# open-race-scale-pi-zero-board-v_02.net
KiCad netlist of a schematic drawn in EAGLE
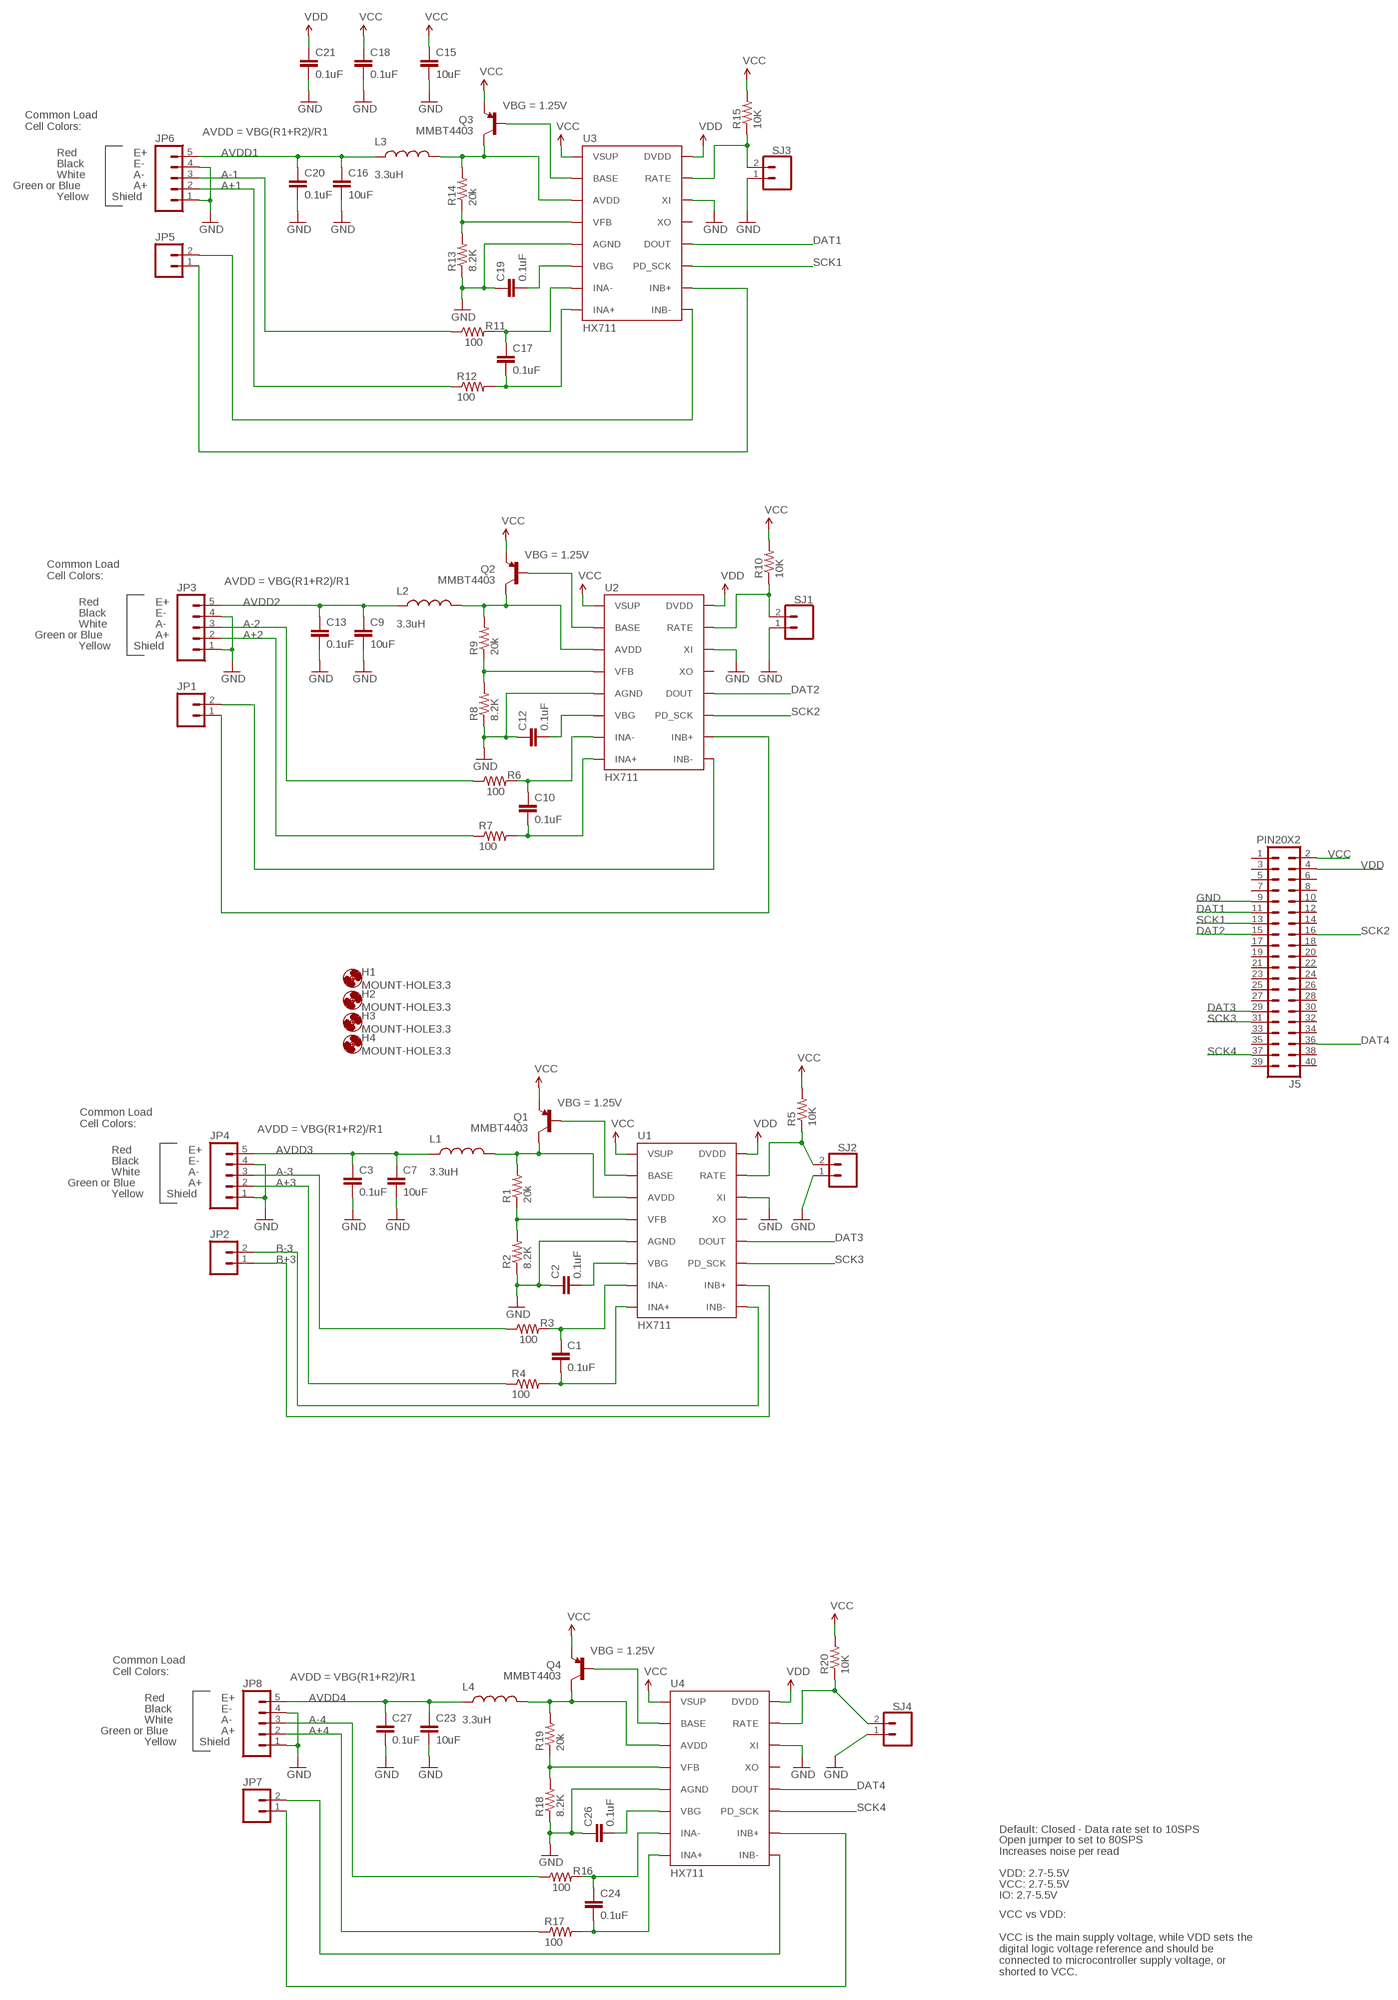
[diagram p0: schematic, sheet 1]

(export (version "E")
  (design (tool "Eeschema 10.0.6"))
  (components
    (comp (ref "C1")
      (value "0.1uF")
      (footprint "eagle-import:0603-CAP")
      (libsource (lib "eagle-import") (part "0.1UF-25V-5%(0603)"))
    )
    (comp (ref "C2")
      (value "0.1uF")
      (footprint "eagle-import:0603-CAP")
      (libsource (lib "eagle-import") (part "0.1UF-25V-5%(0603)"))
    )
    (comp (ref "C3")
      (value "0.1uF")
      (footprint "eagle-import:0603-CAP")
      (libsource (lib "eagle-import") (part "0.1UF-25V-5%(0603)"))
    )
    (comp (ref "C7")
      (value "10uF")
      (footprint "eagle-import:1210")
      (libsource (lib "eagle-import") (part "10UF50V20%(1210)"))
    )
    (comp (ref "C9")
      (value "10uF")
      (footprint "eagle-import:1210")
      (libsource (lib "eagle-import") (part "10UF50V20%(1210)"))
    )
    (comp (ref "C10")
      (value "0.1uF")
      (footprint "eagle-import:0603-CAP")
      (libsource (lib "eagle-import") (part "0.1UF-25V-5%(0603)"))
    )
    (comp (ref "C12")
      (value "0.1uF")
      (footprint "eagle-import:0603-CAP")
      (libsource (lib "eagle-import") (part "0.1UF-25V-5%(0603)"))
    )
    (comp (ref "C13")
      (value "0.1uF")
      (footprint "eagle-import:0603-CAP")
      (libsource (lib "eagle-import") (part "0.1UF-25V-5%(0603)"))
    )
    (comp (ref "C15")
      (value "10uF")
      (footprint "eagle-import:1210")
      (libsource (lib "eagle-import") (part "10UF50V20%(1210)"))
    )
    (comp (ref "C16")
      (value "10uF")
      (footprint "eagle-import:1210")
      (libsource (lib "eagle-import") (part "10UF50V20%(1210)"))
    )
    (comp (ref "C17")
      (value "0.1uF")
      (footprint "eagle-import:0603-CAP")
      (libsource (lib "eagle-import") (part "0.1UF-25V-5%(0603)"))
    )
    (comp (ref "C18")
      (value "0.1uF")
      (footprint "eagle-import:0603-CAP")
      (libsource (lib "eagle-import") (part "0.1UF-25V-5%(0603)"))
    )
    (comp (ref "C19")
      (value "0.1uF")
      (footprint "eagle-import:0603-CAP")
      (libsource (lib "eagle-import") (part "0.1UF-25V-5%(0603)"))
    )
    (comp (ref "C20")
      (value "0.1uF")
      (footprint "eagle-import:0603-CAP")
      (libsource (lib "eagle-import") (part "0.1UF-25V-5%(0603)"))
    )
    (comp (ref "C21")
      (value "0.1uF")
      (footprint "eagle-import:0603-CAP")
      (libsource (lib "eagle-import") (part "0.1UF-25V-5%(0603)"))
    )
    (comp (ref "C23")
      (value "10uF")
      (footprint "eagle-import:1210")
      (libsource (lib "eagle-import") (part "10UF50V20%(1210)"))
    )
    (comp (ref "C24")
      (value "0.1uF")
      (footprint "eagle-import:0603-CAP")
      (libsource (lib "eagle-import") (part "0.1UF-25V-5%(0603)"))
    )
    (comp (ref "C26")
      (value "0.1uF")
      (footprint "eagle-import:0603-CAP")
      (libsource (lib "eagle-import") (part "0.1UF-25V-5%(0603)"))
    )
    (comp (ref "C27")
      (value "0.1uF")
      (footprint "eagle-import:0603-CAP")
      (libsource (lib "eagle-import") (part "0.1UF-25V-5%(0603)"))
    )
    (comp (ref "H1")
      (value "MOUNT-HOLE3.3")
      (footprint "eagle-import:3,3")
      (libsource (lib "eagle-import") (part "MOUNT-HOLE3.3"))
    )
    (comp (ref "H2")
      (value "MOUNT-HOLE3.3")
      (footprint "eagle-import:3,3")
      (libsource (lib "eagle-import") (part "MOUNT-HOLE3.3"))
    )
    (comp (ref "H3")
      (value "MOUNT-HOLE3.3")
      (footprint "eagle-import:3,3")
      (libsource (lib "eagle-import") (part "MOUNT-HOLE3.3"))
    )
    (comp (ref "H4")
      (value "MOUNT-HOLE3.3")
      (footprint "eagle-import:3,3")
      (libsource (lib "eagle-import") (part "MOUNT-HOLE3.3"))
    )
    (comp (ref "J5")
      (value "PIN20X2")
      (footprint "eagle-import:PIN_20X2")
      (libsource (lib "eagle-import") (part "PIN20X2"))
    )
    (comp (ref "JP1")
      (value "M02PTH")
      (footprint "eagle-import:1X02@1")
      (libsource (lib "eagle-import") (part "M02PTH"))
    )
    (comp (ref "JP2")
      (value "M02PTH")
      (footprint "eagle-import:1X02@1")
      (libsource (lib "eagle-import") (part "M02PTH"))
    )
    (comp (ref "JP3")
      (value "M05PTH")
      (footprint "eagle-import:1X05")
      (libsource (lib "eagle-import") (part "M05PTH"))
    )
    (comp (ref "JP4")
      (value "M05PTH")
      (footprint "eagle-import:1X05")
      (libsource (lib "eagle-import") (part "M05PTH"))
    )
    (comp (ref "JP5")
      (value "M02PTH")
      (footprint "eagle-import:1X02@1")
      (libsource (lib "eagle-import") (part "M02PTH"))
    )
    (comp (ref "JP6")
      (value "M05PTH")
      (footprint "eagle-import:1X05")
      (libsource (lib "eagle-import") (part "M05PTH"))
    )
    (comp (ref "JP7")
      (value "M02PTH")
      (footprint "eagle-import:1X02@1")
      (libsource (lib "eagle-import") (part "M02PTH"))
    )
    (comp (ref "JP8")
      (value "M05PTH")
      (footprint "eagle-import:1X05")
      (libsource (lib "eagle-import") (part "M05PTH"))
    )
    (comp (ref "L1")
      (value "3.3uH")
      (footprint "eagle-import:0805")
      (libsource (lib "eagle-import") (part "INDUCTOR0805-IND"))
    )
    (comp (ref "L2")
      (value "3.3uH")
      (footprint "eagle-import:0805")
      (libsource (lib "eagle-import") (part "INDUCTOR0805-IND"))
    )
    (comp (ref "L3")
      (value "3.3uH")
      (footprint "eagle-import:0805")
      (libsource (lib "eagle-import") (part "INDUCTOR0805-IND"))
    )
    (comp (ref "L4")
      (value "3.3uH")
      (footprint "eagle-import:0805")
      (libsource (lib "eagle-import") (part "INDUCTOR0805-IND"))
    )
    (comp (ref "Q1")
      (value "MMBT4403")
      (footprint "eagle-import:SOT23-3")
      (libsource (lib "eagle-import") (part "TRANSISTOR_PNPMMBT4403"))
    )
    (comp (ref "Q2")
      (value "MMBT4403")
      (footprint "eagle-import:SOT23-3")
      (libsource (lib "eagle-import") (part "TRANSISTOR_PNPMMBT4403"))
    )
    (comp (ref "Q3")
      (value "MMBT4403")
      (footprint "eagle-import:SOT23-3")
      (libsource (lib "eagle-import") (part "TRANSISTOR_PNPMMBT4403"))
    )
    (comp (ref "Q4")
      (value "MMBT4403")
      (footprint "eagle-import:SOT23-3")
      (libsource (lib "eagle-import") (part "TRANSISTOR_PNPMMBT4403"))
    )
    (comp (ref "R1")
      (value "20k")
      (footprint "eagle-import:0603-RES")
      (libsource (lib "eagle-import") (part "20KOHM1/10W1%(0603)"))
    )
    (comp (ref "R2")
      (value "8.2K")
      (footprint "eagle-import:0603-RES")
      (libsource (lib "eagle-import") (part "8.2KOHM-1/10W-5%(0603)"))
    )
    (comp (ref "R3")
      (value "100")
      (footprint "eagle-import:0603-RES")
      (libsource (lib "eagle-import") (part "100OHM-1/10W-1%(0603)"))
    )
    (comp (ref "R4")
      (value "100")
      (footprint "eagle-import:0603-RES")
      (libsource (lib "eagle-import") (part "100OHM-1/10W-1%(0603)"))
    )
    (comp (ref "R5")
      (value "10K")
      (footprint "eagle-import:0603-RES")
      (libsource (lib "eagle-import") (part "10KOHM-1/10W-1%(0603)0603"))
    )
    (comp (ref "R6")
      (value "100")
      (footprint "eagle-import:0603-RES")
      (libsource (lib "eagle-import") (part "100OHM-1/10W-1%(0603)"))
    )
    (comp (ref "R7")
      (value "100")
      (footprint "eagle-import:0603-RES")
      (libsource (lib "eagle-import") (part "100OHM-1/10W-1%(0603)"))
    )
    (comp (ref "R8")
      (value "8.2K")
      (footprint "eagle-import:0603-RES")
      (libsource (lib "eagle-import") (part "8.2KOHM-1/10W-5%(0603)"))
    )
    (comp (ref "R9")
      (value "20k")
      (footprint "eagle-import:0603-RES")
      (libsource (lib "eagle-import") (part "20KOHM1/10W1%(0603)"))
    )
    (comp (ref "R10")
      (value "10K")
      (footprint "eagle-import:0603-RES")
      (libsource (lib "eagle-import") (part "10KOHM-1/10W-1%(0603)0603"))
    )
    (comp (ref "R11")
      (value "100")
      (footprint "eagle-import:0603-RES")
      (libsource (lib "eagle-import") (part "100OHM-1/10W-1%(0603)"))
    )
    (comp (ref "R12")
      (value "100")
      (footprint "eagle-import:0603-RES")
      (libsource (lib "eagle-import") (part "100OHM-1/10W-1%(0603)"))
    )
    (comp (ref "R13")
      (value "8.2K")
      (footprint "eagle-import:0603-RES")
      (libsource (lib "eagle-import") (part "8.2KOHM-1/10W-5%(0603)"))
    )
    (comp (ref "R14")
      (value "20k")
      (footprint "eagle-import:0603-RES")
      (libsource (lib "eagle-import") (part "20KOHM1/10W1%(0603)"))
    )
    (comp (ref "R15")
      (value "10K")
      (footprint "eagle-import:0603-RES")
      (libsource (lib "eagle-import") (part "10KOHM-1/10W-1%(0603)0603"))
    )
    (comp (ref "R16")
      (value "100")
      (footprint "eagle-import:0603-RES")
      (libsource (lib "eagle-import") (part "100OHM-1/10W-1%(0603)"))
    )
    (comp (ref "R17")
      (value "100")
      (footprint "eagle-import:0603-RES")
      (libsource (lib "eagle-import") (part "100OHM-1/10W-1%(0603)"))
    )
    (comp (ref "R18")
      (value "8.2K")
      (footprint "eagle-import:0603-RES")
      (libsource (lib "eagle-import") (part "8.2KOHM-1/10W-5%(0603)"))
    )
    (comp (ref "R19")
      (value "20k")
      (footprint "eagle-import:0603-RES")
      (libsource (lib "eagle-import") (part "20KOHM1/10W1%(0603)"))
    )
    (comp (ref "R20")
      (value "10K")
      (footprint "eagle-import:0603-RES")
      (libsource (lib "eagle-import") (part "10KOHM-1/10W-1%(0603)0603"))
    )
    (comp (ref "SJ1")
      (value "CONN_02")
      (footprint "eagle-import:1X02")
      (libsource (lib "eagle-import") (part "CONN_02"))
    )
    (comp (ref "SJ2")
      (value "CONN_02")
      (footprint "eagle-import:1X02")
      (libsource (lib "eagle-import") (part "CONN_02"))
    )
    (comp (ref "SJ3")
      (value "CONN_02")
      (footprint "eagle-import:1X02")
      (libsource (lib "eagle-import") (part "CONN_02"))
    )
    (comp (ref "SJ4")
      (value "CONN_02")
      (footprint "eagle-import:1X02")
      (libsource (lib "eagle-import") (part "CONN_02"))
    )
    (comp (ref "U1")
      (value "HX711")
      (footprint "eagle-import:SO16")
      (libsource (lib "eagle-import") (part "HX711HX711"))
    )
    (comp (ref "U2")
      (value "HX711")
      (footprint "eagle-import:SO16")
      (libsource (lib "eagle-import") (part "HX711HX711"))
    )
    (comp (ref "U3")
      (value "HX711")
      (footprint "eagle-import:SO16")
      (libsource (lib "eagle-import") (part "HX711HX711"))
    )
    (comp (ref "U4")
      (value "HX711")
      (footprint "eagle-import:SO16")
      (libsource (lib "eagle-import") (part "HX711HX711"))
    )
  )
  (nets
    (net (code "1") (name "/A+1") (class "Default")
      (node (ref "JP6") (pin "2") (pinfunction "2_2") (pintype "passive"))
      (node (ref "R12") (pin "1") (pinfunction "1_1") (pintype "passive"))
    )
    (net (code "2") (name "/A+2") (class "Default")
      (node (ref "JP3") (pin "2") (pinfunction "2_2") (pintype "passive"))
      (node (ref "R7") (pin "1") (pinfunction "1_1") (pintype "passive"))
    )
    (net (code "3") (name "/A+3") (class "Default")
      (node (ref "JP4") (pin "2") (pinfunction "2_2") (pintype "passive"))
      (node (ref "R4") (pin "1") (pinfunction "1_1") (pintype "passive"))
    )
    (net (code "4") (name "/A+4") (class "Default")
      (node (ref "JP8") (pin "2") (pinfunction "2_2") (pintype "passive"))
      (node (ref "R17") (pin "1") (pinfunction "1_1") (pintype "passive"))
    )
    (net (code "5") (name "/A-1") (class "Default")
      (node (ref "JP6") (pin "3") (pinfunction "3_3") (pintype "passive"))
      (node (ref "R11") (pin "1") (pinfunction "1_1") (pintype "passive"))
    )
    (net (code "6") (name "/A-2") (class "Default")
      (node (ref "JP3") (pin "3") (pinfunction "3_3") (pintype "passive"))
      (node (ref "R6") (pin "1") (pinfunction "1_1") (pintype "passive"))
    )
    (net (code "7") (name "/A-3") (class "Default")
      (node (ref "JP4") (pin "3") (pinfunction "3_3") (pintype "passive"))
      (node (ref "R3") (pin "1") (pinfunction "1_1") (pintype "passive"))
    )
    (net (code "8") (name "/A-4") (class "Default")
      (node (ref "JP8") (pin "3") (pinfunction "3_3") (pintype "passive"))
      (node (ref "R16") (pin "1") (pinfunction "1_1") (pintype "passive"))
    )
    (net (code "9") (name "/AVDD1") (class "Default")
      (node (ref "C16") (pin "1") (pinfunction "1_1") (pintype "passive"))
      (node (ref "C20") (pin "1") (pinfunction "1_1") (pintype "passive"))
      (node (ref "JP6") (pin "5") (pinfunction "5_5") (pintype "passive"))
      (node (ref "L3") (pin "1") (pinfunction "1_1") (pintype "passive"))
    )
    (net (code "10") (name "/AVDD2") (class "Default")
      (node (ref "C13") (pin "1") (pinfunction "1_1") (pintype "passive"))
      (node (ref "C9") (pin "1") (pinfunction "1_1") (pintype "passive"))
      (node (ref "JP3") (pin "5") (pinfunction "5_5") (pintype "passive"))
      (node (ref "L2") (pin "1") (pinfunction "1_1") (pintype "passive"))
    )
    (net (code "11") (name "/AVDD3") (class "Default")
      (node (ref "C3") (pin "1") (pinfunction "1_1") (pintype "passive"))
      (node (ref "C7") (pin "1") (pinfunction "1_1") (pintype "passive"))
      (node (ref "JP4") (pin "5") (pinfunction "5_5") (pintype "passive"))
      (node (ref "L1") (pin "1") (pinfunction "1_1") (pintype "passive"))
    )
    (net (code "12") (name "/AVDD4") (class "Default")
      (node (ref "C23") (pin "1") (pinfunction "1_1") (pintype "passive"))
      (node (ref "C27") (pin "1") (pinfunction "1_1") (pintype "passive"))
      (node (ref "JP8") (pin "5") (pinfunction "5_5") (pintype "passive"))
      (node (ref "L4") (pin "1") (pinfunction "1_1") (pintype "passive"))
    )
    (net (code "13") (name "/B+3") (class "Default")
      (node (ref "JP2") (pin "1") (pinfunction "1_1") (pintype "passive"))
      (node (ref "U1") (pin "10") (pinfunction "INB+_10") (pintype "bidirectional"))
    )
    (net (code "14") (name "/B-3") (class "Default")
      (node (ref "JP2") (pin "2") (pinfunction "2_2") (pintype "passive"))
      (node (ref "U1") (pin "9") (pinfunction "INB-_9") (pintype "bidirectional"))
    )
    (net (code "15") (name "/DAT1") (class "Default")
      (node (ref "J5") (pin "11") (pinfunction "11_11") (pintype "passive"))
      (node (ref "U3") (pin "12") (pinfunction "DOUT_12") (pintype "bidirectional"))
    )
    (net (code "16") (name "/DAT2") (class "Default")
      (node (ref "J5") (pin "15") (pinfunction "15_15") (pintype "passive"))
      (node (ref "U2") (pin "12") (pinfunction "DOUT_12") (pintype "bidirectional"))
    )
    (net (code "17") (name "/DAT3") (class "Default")
      (node (ref "J5") (pin "29") (pinfunction "29_29") (pintype "passive"))
      (node (ref "U1") (pin "12") (pinfunction "DOUT_12") (pintype "bidirectional"))
    )
    (net (code "18") (name "/DAT4") (class "Default")
      (node (ref "J5") (pin "36") (pinfunction "36_36") (pintype "passive"))
      (node (ref "U4") (pin "12") (pinfunction "DOUT_12") (pintype "bidirectional"))
    )
    (net (code "19") (name "/SCK1") (class "Default")
      (node (ref "J5") (pin "13") (pinfunction "13_13") (pintype "passive"))
      (node (ref "U3") (pin "11") (pinfunction "PD_SCK_11") (pintype "bidirectional"))
    )
    (net (code "20") (name "/SCK2") (class "Default")
      (node (ref "J5") (pin "16") (pinfunction "16_16") (pintype "passive"))
      (node (ref "U2") (pin "11") (pinfunction "PD_SCK_11") (pintype "bidirectional"))
    )
    (net (code "21") (name "/SCK3") (class "Default")
      (node (ref "J5") (pin "31") (pinfunction "31_31") (pintype "passive"))
      (node (ref "U1") (pin "11") (pinfunction "PD_SCK_11") (pintype "bidirectional"))
    )
    (net (code "22") (name "/SCK4") (class "Default")
      (node (ref "J5") (pin "37") (pinfunction "37_37") (pintype "passive"))
      (node (ref "U4") (pin "11") (pinfunction "PD_SCK_11") (pintype "bidirectional"))
    )
    (net (code "23") (name "GND") (class "Default")
      (node (ref "C12") (pin "1") (pinfunction "1_1") (pintype "passive"))
      (node (ref "C13") (pin "2") (pinfunction "2_2") (pintype "passive"))
      (node (ref "C15") (pin "2") (pinfunction "2_2") (pintype "passive"))
      (node (ref "C16") (pin "2") (pinfunction "2_2") (pintype "passive"))
      (node (ref "C18") (pin "2") (pinfunction "2_2") (pintype "passive"))
      (node (ref "C19") (pin "1") (pinfunction "1_1") (pintype "passive"))
      (node (ref "C2") (pin "1") (pinfunction "1_1") (pintype "passive"))
      (node (ref "C20") (pin "2") (pinfunction "2_2") (pintype "passive"))
      (node (ref "C21") (pin "2") (pinfunction "2_2") (pintype "passive"))
      (node (ref "C23") (pin "2") (pinfunction "2_2") (pintype "passive"))
      (node (ref "C26") (pin "1") (pinfunction "1_1") (pintype "passive"))
      (node (ref "C27") (pin "2") (pinfunction "2_2") (pintype "passive"))
      (node (ref "C3") (pin "2") (pinfunction "2_2") (pintype "passive"))
      (node (ref "C7") (pin "2") (pinfunction "2_2") (pintype "passive"))
      (node (ref "C9") (pin "2") (pinfunction "2_2") (pintype "passive"))
      (node (ref "J5") (pin "9") (pinfunction "9_9") (pintype "passive"))
      (node (ref "JP3") (pin "1") (pinfunction "1_1") (pintype "passive"))
      (node (ref "JP3") (pin "4") (pinfunction "4_4") (pintype "passive"))
      (node (ref "JP4") (pin "1") (pinfunction "1_1") (pintype "passive"))
      (node (ref "JP4") (pin "4") (pinfunction "4_4") (pintype "passive"))
      (node (ref "JP6") (pin "1") (pinfunction "1_1") (pintype "passive"))
      (node (ref "JP6") (pin "4") (pinfunction "4_4") (pintype "passive"))
      (node (ref "JP8") (pin "1") (pinfunction "1_1") (pintype "passive"))
      (node (ref "JP8") (pin "4") (pinfunction "4_4") (pintype "passive"))
      (node (ref "R13") (pin "1") (pinfunction "1_1") (pintype "passive"))
      (node (ref "R18") (pin "1") (pinfunction "1_1") (pintype "passive"))
      (node (ref "R2") (pin "1") (pinfunction "1_1") (pintype "passive"))
      (node (ref "R8") (pin "1") (pinfunction "1_1") (pintype "passive"))
      (node (ref "SJ1") (pin "1") (pinfunction "1_1") (pintype "passive"))
      (node (ref "SJ2") (pin "1") (pinfunction "1_1") (pintype "passive"))
      (node (ref "SJ3") (pin "1") (pinfunction "1_1") (pintype "passive"))
      (node (ref "SJ4") (pin "1") (pinfunction "1_1") (pintype "passive"))
      (node (ref "U1") (pin "14") (pinfunction "XI_14") (pintype "bidirectional"))
      (node (ref "U1") (pin "5") (pinfunction "AGND_5") (pintype "bidirectional"))
      (node (ref "U2") (pin "14") (pinfunction "XI_14") (pintype "bidirectional"))
      (node (ref "U2") (pin "5") (pinfunction "AGND_5") (pintype "bidirectional"))
      (node (ref "U3") (pin "14") (pinfunction "XI_14") (pintype "bidirectional"))
      (node (ref "U3") (pin "5") (pinfunction "AGND_5") (pintype "bidirectional"))
      (node (ref "U4") (pin "14") (pinfunction "XI_14") (pintype "bidirectional"))
      (node (ref "U4") (pin "5") (pinfunction "AGND_5") (pintype "bidirectional"))
    )
    (net (code "24") (name "Net-(Q1-B)") (class "Default")
      (node (ref "Q1") (pin "1") (pinfunction "B_1") (pintype "passive"))
      (node (ref "U1") (pin "2") (pinfunction "BASE_2") (pintype "bidirectional"))
    )
    (net (code "25") (name "Net-(Q1-C)") (class "Default")
      (node (ref "L1") (pin "2") (pinfunction "2_2") (pintype "passive"))
      (node (ref "Q1") (pin "3") (pinfunction "C_3") (pintype "passive"))
      (node (ref "R1") (pin "2") (pinfunction "2_2") (pintype "passive"))
      (node (ref "U1") (pin "3") (pinfunction "AVDD_3") (pintype "bidirectional"))
    )
    (net (code "26") (name "Net-(Q2-B)") (class "Default")
      (node (ref "Q2") (pin "1") (pinfunction "B_1") (pintype "passive"))
      (node (ref "U2") (pin "2") (pinfunction "BASE_2") (pintype "bidirectional"))
    )
    (net (code "27") (name "Net-(Q2-C)") (class "Default")
      (node (ref "L2") (pin "2") (pinfunction "2_2") (pintype "passive"))
      (node (ref "Q2") (pin "3") (pinfunction "C_3") (pintype "passive"))
      (node (ref "R9") (pin "2") (pinfunction "2_2") (pintype "passive"))
      (node (ref "U2") (pin "3") (pinfunction "AVDD_3") (pintype "bidirectional"))
    )
    (net (code "28") (name "Net-(Q3-B)") (class "Default")
      (node (ref "Q3") (pin "1") (pinfunction "B_1") (pintype "passive"))
      (node (ref "U3") (pin "2") (pinfunction "BASE_2") (pintype "bidirectional"))
    )
    (net (code "29") (name "Net-(Q3-C)") (class "Default")
      (node (ref "L3") (pin "2") (pinfunction "2_2") (pintype "passive"))
      (node (ref "Q3") (pin "3") (pinfunction "C_3") (pintype "passive"))
      (node (ref "R14") (pin "2") (pinfunction "2_2") (pintype "passive"))
      (node (ref "U3") (pin "3") (pinfunction "AVDD_3") (pintype "bidirectional"))
    )
    (net (code "30") (name "Net-(Q4-B)") (class "Default")
      (node (ref "Q4") (pin "1") (pinfunction "B_1") (pintype "passive"))
      (node (ref "U4") (pin "2") (pinfunction "BASE_2") (pintype "bidirectional"))
    )
    (net (code "31") (name "Net-(Q4-C)") (class "Default")
      (node (ref "L4") (pin "2") (pinfunction "2_2") (pintype "passive"))
      (node (ref "Q4") (pin "3") (pinfunction "C_3") (pintype "passive"))
      (node (ref "R19") (pin "2") (pinfunction "2_2") (pintype "passive"))
      (node (ref "U4") (pin "3") (pinfunction "AVDD_3") (pintype "bidirectional"))
    )
    (net (code "32") (name "Net-(U1-INA+)") (class "Default")
      (node (ref "C1") (pin "2") (pinfunction "2_2") (pintype "passive"))
      (node (ref "R4") (pin "2") (pinfunction "2_2") (pintype "passive"))
      (node (ref "U1") (pin "8") (pinfunction "INA+_8") (pintype "bidirectional"))
    )
    (net (code "33") (name "Net-(U1-INA-)") (class "Default")
      (node (ref "C1") (pin "1") (pinfunction "1_1") (pintype "passive"))
      (node (ref "R3") (pin "2") (pinfunction "2_2") (pintype "passive"))
      (node (ref "U1") (pin "7") (pinfunction "INA-_7") (pintype "bidirectional"))
    )
    (net (code "34") (name "Net-(U1-RATE)") (class "Default")
      (node (ref "R5") (pin "1") (pinfunction "1_1") (pintype "passive"))
      (node (ref "SJ2") (pin "2") (pinfunction "2_2") (pintype "passive"))
      (node (ref "U1") (pin "15") (pinfunction "RATE_15") (pintype "bidirectional"))
    )
    (net (code "35") (name "Net-(U1-VBG)") (class "Default")
      (node (ref "C2") (pin "2") (pinfunction "2_2") (pintype "passive"))
      (node (ref "U1") (pin "6") (pinfunction "VBG_6") (pintype "bidirectional"))
    )
    (net (code "36") (name "Net-(U1-VFB)") (class "Default")
      (node (ref "R1") (pin "1") (pinfunction "1_1") (pintype "passive"))
      (node (ref "R2") (pin "2") (pinfunction "2_2") (pintype "passive"))
      (node (ref "U1") (pin "4") (pinfunction "VFB_4") (pintype "bidirectional"))
    )
    (net (code "37") (name "Net-(U2-INA+)") (class "Default")
      (node (ref "C10") (pin "2") (pinfunction "2_2") (pintype "passive"))
      (node (ref "R7") (pin "2") (pinfunction "2_2") (pintype "passive"))
      (node (ref "U2") (pin "8") (pinfunction "INA+_8") (pintype "bidirectional"))
    )
    (net (code "38") (name "Net-(U2-INA-)") (class "Default")
      (node (ref "C10") (pin "1") (pinfunction "1_1") (pintype "passive"))
      (node (ref "R6") (pin "2") (pinfunction "2_2") (pintype "passive"))
      (node (ref "U2") (pin "7") (pinfunction "INA-_7") (pintype "bidirectional"))
    )
    (net (code "39") (name "Net-(U2-INB+)") (class "Default")
      (node (ref "JP1") (pin "1") (pinfunction "1_1") (pintype "passive"))
      (node (ref "U2") (pin "10") (pinfunction "INB+_10") (pintype "bidirectional"))
    )
    (net (code "40") (name "Net-(U2-INB-)") (class "Default")
      (node (ref "JP1") (pin "2") (pinfunction "2_2") (pintype "passive"))
      (node (ref "U2") (pin "9") (pinfunction "INB-_9") (pintype "bidirectional"))
    )
    (net (code "41") (name "Net-(U2-RATE)") (class "Default")
      (node (ref "R10") (pin "1") (pinfunction "1_1") (pintype "passive"))
      (node (ref "SJ1") (pin "2") (pinfunction "2_2") (pintype "passive"))
      (node (ref "U2") (pin "15") (pinfunction "RATE_15") (pintype "bidirectional"))
    )
    (net (code "42") (name "Net-(U2-VBG)") (class "Default")
      (node (ref "C12") (pin "2") (pinfunction "2_2") (pintype "passive"))
      (node (ref "U2") (pin "6") (pinfunction "VBG_6") (pintype "bidirectional"))
    )
    (net (code "43") (name "Net-(U2-VFB)") (class "Default")
      (node (ref "R8") (pin "2") (pinfunction "2_2") (pintype "passive"))
      (node (ref "R9") (pin "1") (pinfunction "1_1") (pintype "passive"))
      (node (ref "U2") (pin "4") (pinfunction "VFB_4") (pintype "bidirectional"))
    )
    (net (code "44") (name "Net-(U3-INA+)") (class "Default")
      (node (ref "C17") (pin "2") (pinfunction "2_2") (pintype "passive"))
      (node (ref "R12") (pin "2") (pinfunction "2_2") (pintype "passive"))
      (node (ref "U3") (pin "8") (pinfunction "INA+_8") (pintype "bidirectional"))
    )
    (net (code "45") (name "Net-(U3-INA-)") (class "Default")
      (node (ref "C17") (pin "1") (pinfunction "1_1") (pintype "passive"))
      (node (ref "R11") (pin "2") (pinfunction "2_2") (pintype "passive"))
      (node (ref "U3") (pin "7") (pinfunction "INA-_7") (pintype "bidirectional"))
    )
    (net (code "46") (name "Net-(U3-INB+)") (class "Default")
      (node (ref "JP5") (pin "1") (pinfunction "1_1") (pintype "passive"))
      (node (ref "U3") (pin "10") (pinfunction "INB+_10") (pintype "bidirectional"))
    )
    (net (code "47") (name "Net-(U3-INB-)") (class "Default")
      (node (ref "JP5") (pin "2") (pinfunction "2_2") (pintype "passive"))
      (node (ref "U3") (pin "9") (pinfunction "INB-_9") (pintype "bidirectional"))
    )
    (net (code "48") (name "Net-(U3-RATE)") (class "Default")
      (node (ref "R15") (pin "1") (pinfunction "1_1") (pintype "passive"))
      (node (ref "SJ3") (pin "2") (pinfunction "2_2") (pintype "passive"))
      (node (ref "U3") (pin "15") (pinfunction "RATE_15") (pintype "bidirectional"))
    )
    (net (code "49") (name "Net-(U3-VBG)") (class "Default")
      (node (ref "C19") (pin "2") (pinfunction "2_2") (pintype "passive"))
      (node (ref "U3") (pin "6") (pinfunction "VBG_6") (pintype "bidirectional"))
    )
    (net (code "50") (name "Net-(U3-VFB)") (class "Default")
      (node (ref "R13") (pin "2") (pinfunction "2_2") (pintype "passive"))
      (node (ref "R14") (pin "1") (pinfunction "1_1") (pintype "passive"))
      (node (ref "U3") (pin "4") (pinfunction "VFB_4") (pintype "bidirectional"))
    )
    (net (code "51") (name "Net-(U4-INA+)") (class "Default")
      (node (ref "C24") (pin "2") (pinfunction "2_2") (pintype "passive"))
      (node (ref "R17") (pin "2") (pinfunction "2_2") (pintype "passive"))
      (node (ref "U4") (pin "8") (pinfunction "INA+_8") (pintype "bidirectional"))
    )
    (net (code "52") (name "Net-(U4-INA-)") (class "Default")
      (node (ref "C24") (pin "1") (pinfunction "1_1") (pintype "passive"))
      (node (ref "R16") (pin "2") (pinfunction "2_2") (pintype "passive"))
      (node (ref "U4") (pin "7") (pinfunction "INA-_7") (pintype "bidirectional"))
    )
    (net (code "53") (name "Net-(U4-INB+)") (class "Default")
      (node (ref "JP7") (pin "1") (pinfunction "1_1") (pintype "passive"))
      (node (ref "U4") (pin "10") (pinfunction "INB+_10") (pintype "bidirectional"))
    )
    (net (code "54") (name "Net-(U4-INB-)") (class "Default")
      (node (ref "JP7") (pin "2") (pinfunction "2_2") (pintype "passive"))
      (node (ref "U4") (pin "9") (pinfunction "INB-_9") (pintype "bidirectional"))
    )
    (net (code "55") (name "Net-(U4-RATE)") (class "Default")
      (node (ref "R20") (pin "1") (pinfunction "1_1") (pintype "passive"))
      (node (ref "SJ4") (pin "2") (pinfunction "2_2") (pintype "passive"))
      (node (ref "U4") (pin "15") (pinfunction "RATE_15") (pintype "bidirectional"))
    )
    (net (code "56") (name "Net-(U4-VBG)") (class "Default")
      (node (ref "C26") (pin "2") (pinfunction "2_2") (pintype "passive"))
      (node (ref "U4") (pin "6") (pinfunction "VBG_6") (pintype "bidirectional"))
    )
    (net (code "57") (name "Net-(U4-VFB)") (class "Default")
      (node (ref "R18") (pin "2") (pinfunction "2_2") (pintype "passive"))
      (node (ref "R19") (pin "1") (pinfunction "1_1") (pintype "passive"))
      (node (ref "U4") (pin "4") (pinfunction "VFB_4") (pintype "bidirectional"))
    )
    (net (code "58") (name "VCC") (class "Default")
      (node (ref "C15") (pin "1") (pinfunction "1_1") (pintype "passive"))
      (node (ref "C18") (pin "1") (pinfunction "1_1") (pintype "passive"))
      (node (ref "J5") (pin "2") (pinfunction "2_2") (pintype "passive"))
      (node (ref "Q1") (pin "2") (pinfunction "E_2") (pintype "passive"))
      (node (ref "Q2") (pin "2") (pinfunction "E_2") (pintype "passive"))
      (node (ref "Q3") (pin "2") (pinfunction "E_2") (pintype "passive"))
      (node (ref "Q4") (pin "2") (pinfunction "E_2") (pintype "passive"))
      (node (ref "R10") (pin "2") (pinfunction "2_2") (pintype "passive"))
      (node (ref "R15") (pin "2") (pinfunction "2_2") (pintype "passive"))
      (node (ref "R20") (pin "2") (pinfunction "2_2") (pintype "passive"))
      (node (ref "R5") (pin "2") (pinfunction "2_2") (pintype "passive"))
      (node (ref "U1") (pin "1") (pinfunction "VSUP_1") (pintype "bidirectional"))
      (node (ref "U2") (pin "1") (pinfunction "VSUP_1") (pintype "bidirectional"))
      (node (ref "U3") (pin "1") (pinfunction "VSUP_1") (pintype "bidirectional"))
      (node (ref "U4") (pin "1") (pinfunction "VSUP_1") (pintype "bidirectional"))
    )
    (net (code "59") (name "VDD") (class "Default")
      (node (ref "C21") (pin "1") (pinfunction "1_1") (pintype "passive"))
      (node (ref "J5") (pin "4") (pinfunction "4_4") (pintype "passive"))
      (node (ref "U1") (pin "16") (pinfunction "DVDD_16") (pintype "bidirectional"))
      (node (ref "U2") (pin "16") (pinfunction "DVDD_16") (pintype "bidirectional"))
      (node (ref "U3") (pin "16") (pinfunction "DVDD_16") (pintype "bidirectional"))
      (node (ref "U4") (pin "16") (pinfunction "DVDD_16") (pintype "bidirectional"))
    )
    (net (code "60") (name "unconnected-(J5-Pad1)") (class "Default")
      (node (ref "J5") (pin "1") (pinfunction "1_1") (pintype "passive"))
    )
    (net (code "61") (name "unconnected-(J5-Pad3)") (class "Default")
      (node (ref "J5") (pin "3") (pinfunction "3_3") (pintype "passive"))
    )
    (net (code "62") (name "unconnected-(J5-Pad5)") (class "Default")
      (node (ref "J5") (pin "5") (pinfunction "5_5") (pintype "passive"))
    )
    (net (code "63") (name "unconnected-(J5-Pad6)") (class "Default")
      (node (ref "J5") (pin "6") (pinfunction "6_6") (pintype "passive"))
    )
    (net (code "64") (name "unconnected-(J5-Pad7)") (class "Default")
      (node (ref "J5") (pin "7") (pinfunction "7_7") (pintype "passive"))
    )
    (net (code "65") (name "unconnected-(J5-Pad8)") (class "Default")
      (node (ref "J5") (pin "8") (pinfunction "8_8") (pintype "passive"))
    )
    (net (code "66") (name "unconnected-(J5-Pad10)") (class "Default")
      (node (ref "J5") (pin "10") (pinfunction "10_10") (pintype "passive"))
    )
    (net (code "67") (name "unconnected-(J5-Pad12)") (class "Default")
      (node (ref "J5") (pin "12") (pinfunction "12_12") (pintype "passive"))
    )
    (net (code "68") (name "unconnected-(J5-Pad14)") (class "Default")
      (node (ref "J5") (pin "14") (pinfunction "14_14") (pintype "passive"))
    )
    (net (code "69") (name "unconnected-(J5-Pad17)") (class "Default")
      (node (ref "J5") (pin "17") (pinfunction "17_17") (pintype "passive"))
    )
    (net (code "70") (name "unconnected-(J5-Pad18)") (class "Default")
      (node (ref "J5") (pin "18") (pinfunction "18_18") (pintype "passive"))
    )
    (net (code "71") (name "unconnected-(J5-Pad19)") (class "Default")
      (node (ref "J5") (pin "19") (pinfunction "19_19") (pintype "passive"))
    )
    (net (code "72") (name "unconnected-(J5-Pad20)") (class "Default")
      (node (ref "J5") (pin "20") (pinfunction "20_20") (pintype "passive"))
    )
    (net (code "73") (name "unconnected-(J5-Pad21)") (class "Default")
      (node (ref "J5") (pin "21") (pinfunction "21_21") (pintype "passive"))
    )
    (net (code "74") (name "unconnected-(J5-Pad22)") (class "Default")
      (node (ref "J5") (pin "22") (pinfunction "22_22") (pintype "passive"))
    )
    (net (code "75") (name "unconnected-(J5-Pad23)") (class "Default")
      (node (ref "J5") (pin "23") (pinfunction "23_23") (pintype "passive"))
    )
    (net (code "76") (name "unconnected-(J5-Pad24)") (class "Default")
      (node (ref "J5") (pin "24") (pinfunction "24_24") (pintype "passive"))
    )
    (net (code "77") (name "unconnected-(J5-Pad25)") (class "Default")
      (node (ref "J5") (pin "25") (pinfunction "25_25") (pintype "passive"))
    )
    (net (code "78") (name "unconnected-(J5-Pad26)") (class "Default")
      (node (ref "J5") (pin "26") (pinfunction "26_26") (pintype "passive"))
    )
    (net (code "79") (name "unconnected-(J5-Pad27)") (class "Default")
      (node (ref "J5") (pin "27") (pinfunction "27_27") (pintype "passive"))
    )
    (net (code "80") (name "unconnected-(J5-Pad28)") (class "Default")
      (node (ref "J5") (pin "28") (pinfunction "28_28") (pintype "passive"))
    )
    (net (code "81") (name "unconnected-(J5-Pad30)") (class "Default")
      (node (ref "J5") (pin "30") (pinfunction "30_30") (pintype "passive"))
    )
    (net (code "82") (name "unconnected-(J5-Pad32)") (class "Default")
      (node (ref "J5") (pin "32") (pinfunction "32_32") (pintype "passive"))
    )
    (net (code "83") (name "unconnected-(J5-Pad33)") (class "Default")
      (node (ref "J5") (pin "33") (pinfunction "33_33") (pintype "passive"))
    )
    (net (code "84") (name "unconnected-(J5-Pad34)") (class "Default")
      (node (ref "J5") (pin "34") (pinfunction "34_34") (pintype "passive"))
    )
    (net (code "85") (name "unconnected-(J5-Pad35)") (class "Default")
      (node (ref "J5") (pin "35") (pinfunction "35_35") (pintype "passive"))
    )
    (net (code "86") (name "unconnected-(J5-Pad38)") (class "Default")
      (node (ref "J5") (pin "38") (pinfunction "38_38") (pintype "passive"))
    )
    (net (code "87") (name "unconnected-(J5-Pad39)") (class "Default")
      (node (ref "J5") (pin "39") (pinfunction "39_39") (pintype "passive"))
    )
    (net (code "88") (name "unconnected-(J5-Pad40)") (class "Default")
      (node (ref "J5") (pin "40") (pinfunction "40_40") (pintype "passive"))
    )
    (net (code "89") (name "unconnected-(U1-XO-Pad13)") (class "Default")
      (node (ref "U1") (pin "13") (pinfunction "XO_13") (pintype "bidirectional"))
    )
    (net (code "90") (name "unconnected-(U2-XO-Pad13)") (class "Default")
      (node (ref "U2") (pin "13") (pinfunction "XO_13") (pintype "bidirectional"))
    )
    (net (code "91") (name "unconnected-(U3-XO-Pad13)") (class "Default")
      (node (ref "U3") (pin "13") (pinfunction "XO_13") (pintype "bidirectional"))
    )
    (net (code "92") (name "unconnected-(U4-XO-Pad13)") (class "Default")
      (node (ref "U4") (pin "13") (pinfunction "XO_13") (pintype "bidirectional"))
    )
  )
)
